# ASA.net
KiCad netlist of a schematic drawn in Altium Designer
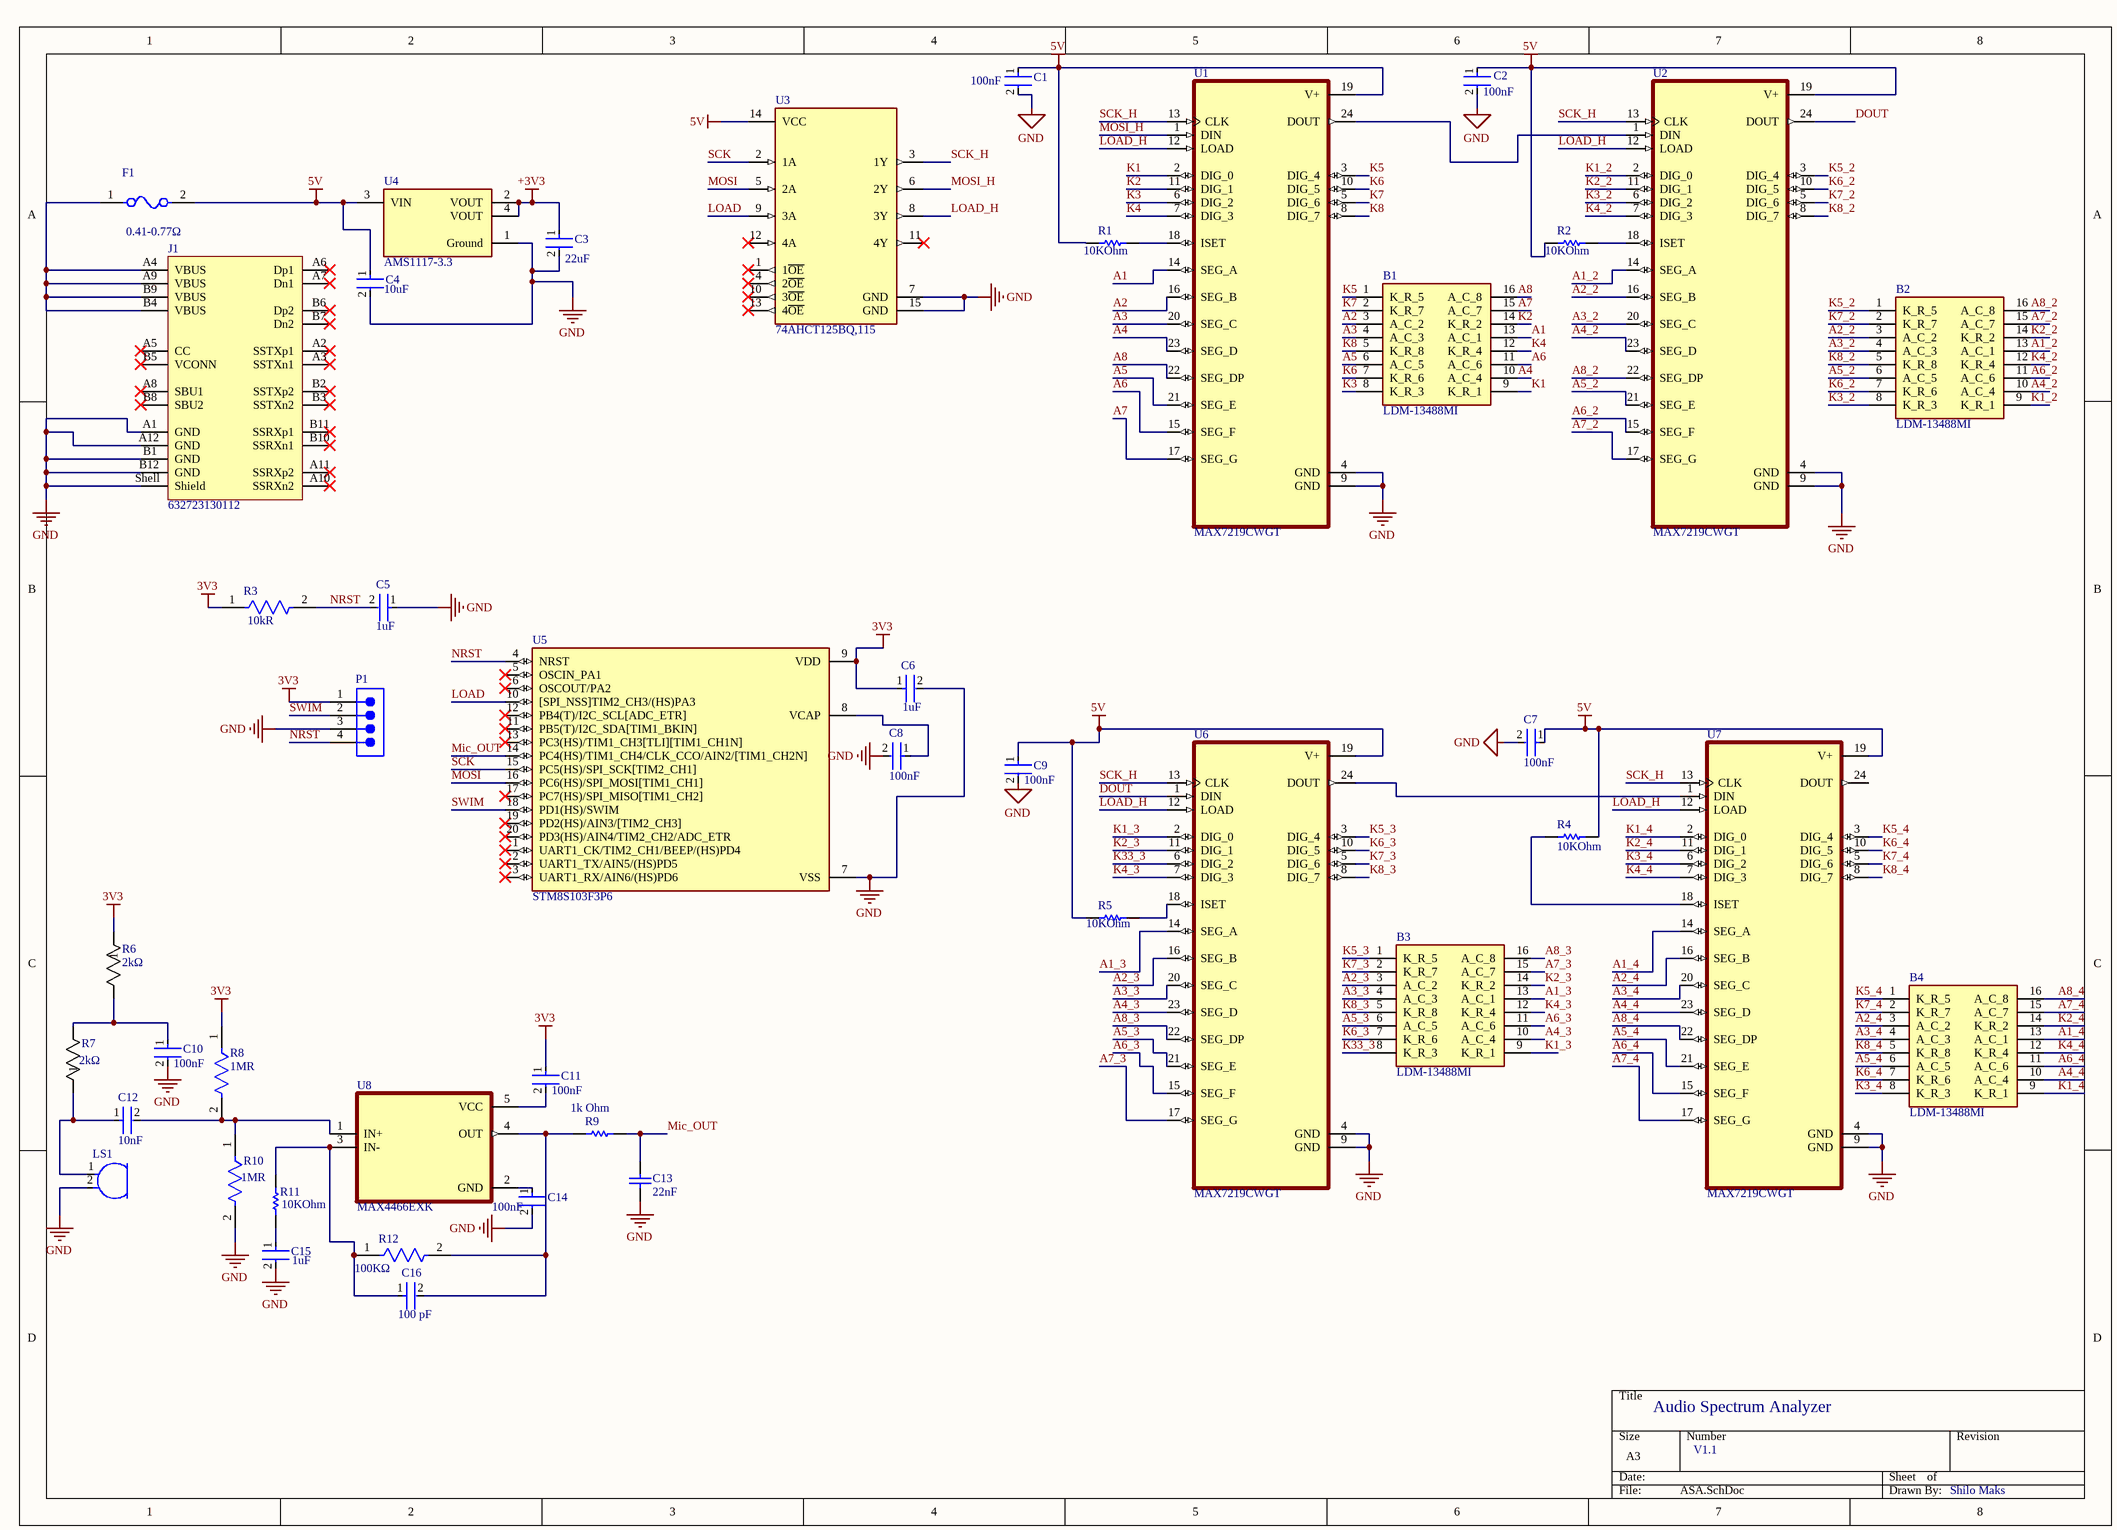
[diagram p0: ASA.SchDoc]

(export (version "E")
  (design (tool "Eeschema 10.0.6"))
  (components
    (comp (ref "B1")
      (value "LDM-13488MI")
      (footprint "LDM13488MI")
      (description "LED MATRIX 8X8 1.3\" 630NM RED CC")
      (fields (field (name "MOUSER PART NUMBER") "696-LDM-13488MI"))
      (libsource (lib "LDM-13488MI") (part "LDM-13488MI"))
    )
    (comp (ref "B2")
      (value "LDM-13488MI")
      (footprint "LDM13488MI")
      (description "LED MATRIX 8X8 1.3\" 630NM RED CC")
      (fields (field (name "MOUSER PART NUMBER") "696-LDM-13488MI"))
      (libsource (lib "LDM-13488MI") (part "LDM-13488MI"))
    )
    (comp (ref "B3")
      (value "LDM-13488MI")
      (footprint "LDM13488MI")
      (description "LED MATRIX 8X8 1.3\" 630NM RED CC")
      (fields (field (name "MOUSER PART NUMBER") "696-LDM-13488MI"))
      (libsource (lib "LDM-13488MI") (part "LDM-13488MI"))
    )
    (comp (ref "B4")
      (value "LDM-13488MI")
      (footprint "LDM13488MI")
      (description "LED MATRIX 8X8 1.3\" 630NM RED CC")
      (fields (field (name "MOUSER PART NUMBER") "696-LDM-13488MI"))
      (libsource (lib "LDM-13488MI") (part "LDM-13488MI"))
    )
    (comp (ref "C1")
      (value "HMK316B7104ML-T")
      (footprint "FP-1206-L_3_2_0_15-W_1_6-IPC_A")
      (description "None")
      (fields (field (name "CAPACITANCE") "100nF") (field (name "TOLERANCE") "20%"))
      (libsource (lib "Altium Content Vault") (part "02cd4be3c70576c341d710602a673aa"))
    )
    (comp (ref "C2")
      (value "HMK316B7104ML-T")
      (footprint "FP-1206-L_3_2_0_15-W_1_6-IPC_A")
      (description "None")
      (fields (field (name "CAPACITANCE") "100nF") (field (name "TOLERANCE") "20%"))
      (libsource (lib "Altium Content Vault") (part "02cd4be3c70576c341d710602a673aa"))
    )
    (comp (ref "C3")
      (value "CC0603MRX5R5BB226")
      (footprint "FP-CC0603-DC-MFG")
      (description "CAP CER 22UF 6.3V X5R 0603")
      (fields (field (name "TOLERANCE") "20%") (field (name "CAPACITANCE") "22uF"))
      (libsource (lib "Altium Content Vault") (part "b4654b650e69147ec39a6b967a45e02"))
    )
    (comp (ref "C4")
      (value "CL21A106MPFNNNF")
      (footprint "FP-CL21-IPC_C")
      (description "CL21 Series 0805 10uF 10V ±20% Tolerance X5R Multilayer Ceramic Chip Capacitor")
      (fields (field (name "TOLERANCE") "20%") (field (name "CAPACITANCE") "10uF"))
      (libsource (lib "Altium Content Vault") (part "b4654b650e69147ec39a6b967a45e02"))
    )
    (comp (ref "C5")
      (value "CL21F105ZAFNNNF")
      (footprint "FP-CL21-IPC_B")
      (description "CL21 Series 0805 1uF 25V -20/+80% Tolerance Y5V Multilayer Ceramic Chip Capacitor")
      (fields (field (name "CAPACITANCE") "1uF") (field (name "TOLERANCE") "80%"))
      (libsource (lib "Altium Content Vault") (part "b4654b650e69147ec39a6b967a45e02"))
    )
    (comp (ref "C6")
      (value "CL21F105ZAFNNNF")
      (footprint "FP-CL21-IPC_B")
      (description "CL21 Series 0805 1uF 25V -20/+80% Tolerance Y5V Multilayer Ceramic Chip Capacitor")
      (fields (field (name "CAPACITANCE") "1uF") (field (name "TOLERANCE") "80%"))
      (libsource (lib "Altium Content Vault") (part "b4654b650e69147ec39a6b967a45e02"))
    )
    (comp (ref "C7")
      (value "HMK316B7104ML-T")
      (footprint "FP-1206-L_3_2_0_15-W_1_6-IPC_A")
      (description "None")
      (fields (field (name "CAPACITANCE") "100nF") (field (name "TOLERANCE") "20%"))
      (libsource (lib "Altium Content Vault") (part "02cd4be3c70576c341d710602a673aa"))
    )
    (comp (ref "C8")
      (value "HMK316B7104ML-T")
      (footprint "FP-1206-L_3_2_0_15-W_1_6-IPC_A")
      (description "None")
      (fields (field (name "CAPACITANCE") "100nF") (field (name "TOLERANCE") "20%"))
      (libsource (lib "Altium Content Vault") (part "02cd4be3c70576c341d710602a673aa"))
    )
    (comp (ref "C9")
      (value "HMK316B7104ML-T")
      (footprint "FP-1206-L_3_2_0_15-W_1_6-IPC_A")
      (description "None")
      (fields (field (name "CAPACITANCE") "100nF") (field (name "TOLERANCE") "20%"))
      (libsource (lib "Altium Content Vault") (part "02cd4be3c70576c341d710602a673aa"))
    )
    (comp (ref "C10")
      (value "HMK316B7104ML-T")
      (footprint "FP-1206-L_3_2_0_15-W_1_6-IPC_A")
      (description "None")
      (fields (field (name "CAPACITANCE") "100nF") (field (name "TOLERANCE") "20%"))
      (libsource (lib "Altium Content Vault") (part "02cd4be3c70576c341d710602a673aa"))
    )
    (comp (ref "C11")
      (value "HMK316B7104ML-T")
      (footprint "FP-1206-L_3_2_0_15-W_1_6-IPC_A")
      (description "None")
      (fields (field (name "CAPACITANCE") "100nF") (field (name "TOLERANCE") "20%"))
      (libsource (lib "Altium Content Vault") (part "02cd4be3c70576c341d710602a673aa"))
    )
    (comp (ref "C12")
      (value "CGA3E2X8R2A103K080AD")
      (footprint "FP-CGA3E-0_3-0_1-IPC_A")
      (description "Cap Ceramic 10nF 100V X8R 10% Pad SMD 0603 +150°C Automotive T/R")
      (fields (field (name "CAPACITANCE") "10nF") (field (name "TOLERANCE") "10%"))
      (libsource (lib "Altium Content Vault") (part "b4654b650e69147ec39a6b967a45e02"))
    )
    (comp (ref "C13")
      (value "22nF")
      (footprint "CAPC1608X92X38NL15T08")
      (fields (field (name "MANUFACTURER") "Vitramon") (field (name "PART NUMBER") "VJ0603Y223KXAAC"))
      (libsource (lib "Altium Content Vault") (part "CAP"))
    )
    (comp (ref "C14")
      (value "HMK316B7104ML-T")
      (footprint "FP-1206-L_3_2_0_15-W_1_6-IPC_A")
      (description "None")
      (fields (field (name "CAPACITANCE") "100nF") (field (name "TOLERANCE") "20%"))
      (libsource (lib "Altium Content Vault") (part "02cd4be3c70576c341d710602a673aa"))
    )
    (comp (ref "C15")
      (value "CL21F105ZAFNNNF")
      (footprint "FP-CL21-IPC_B")
      (description "CL21 Series 0805 1uF 25V -20/+80% Tolerance Y5V Multilayer Ceramic Chip Capacitor")
      (fields (field (name "CAPACITANCE") "1uF") (field (name "TOLERANCE") "80%"))
      (libsource (lib "Altium Content Vault") (part "b4654b650e69147ec39a6b967a45e02"))
    )
    (comp (ref "C16")
      (value "C0402C101K5GACTU")
      (footprint "FP-C0402-BB-MFG")
      (description "CAP CER 100PF 50V 10% NP0 0402")
      (fields
        (field (name "TOLERANCE") "0.1")
        (field (name "CAPACITANCE") "100 pF")
        (field (name "MANUFACTURER") "Kemet")
      )
      (libsource (lib "Altium Content Vault") (part "b4654b650e69147ec39a6b967a45e02"))
    )
    (comp (ref "F1")
      (value "MF-R050")
      (footprint "FP-MF-R050-MFG")
      (description "PTC RESET FUSE 60V 500MA RADIAL")
      (fields
        (field (name "OCTOPART") "https://octopart.com/mf-r050-bourns-19418")
        (field (name "RESISTANCE") "0.41-0.77Ω")
        (field (name "MANUFACTURER") "Bourns")
      )
      (libsource (lib "Altium Content Vault") (part "5bcf9b9f640e542cf0359d10258e979"))
    )
    (comp (ref "J1")
      (value "632723130112")
      (footprint "632723130112")
      (description "WR-COM_USB 3.1_TYPE C_HORIZONTAL")
      (libsource (lib "Altium Content Vault") (part "USB 3.1_Type C_Receptacle_1 Port"))
    )
    (comp (ref "LS1")
      (value "POM-2738P-R")
      (footprint "FP-POM-2738P-R-MFG")
      (description "MIC COND ANALOG OMNI -38DB")
      (fields
        (field (name "MANUFACTURER") "PUI Audio, Inc.")
        (field (name "OCTOPART") "https://octopart.com/pom-2738p-r-pui+audio-19251807")
      )
      (libsource (lib "Altium Content Vault") (part "b2bcf75ddc372d3ce9fb98e3c3a2780"))
    )
    (comp (ref "P1")
      (value "61300411021")
      (footprint "61300411021")
      (libsource (lib "Altium Content Vault") (part "Header_Male_1R_04P"))
    )
    (comp (ref "R1")
      (value "10KOhm")
      (footprint "RESC1206(3216)_M")
      (description "10K 0.25W 5% 1206 (3216 Metric)  SMD")
      (fields (field (name "POWER") "0.25 W") (field (name "TOLERANCE") "5 %"))
      (libsource (lib "Altium Content Vault") (part "RES"))
    )
    (comp (ref "R2")
      (value "10KOhm")
      (footprint "RESC1206(3216)_M")
      (description "10K 0.25W 5% 1206 (3216 Metric)  SMD")
      (fields (field (name "POWER") "0.25 W") (field (name "TOLERANCE") "5 %"))
      (libsource (lib "Altium Content Vault") (part "RES"))
    )
    (comp (ref "R3")
      (value "CR2010-JW-103ELF")
      (footprint "FP-CR2010-IPC_C")
      (description "Thick Film Chip Resistors 2010 10kΩ 0.5W 5% 200ppm/°C")
      (fields (field (name "TOLERANCE") "5%") (field (name "RESISTANCE") "10kR"))
      (libsource (lib "Altium Content Vault") (part "1029c3af85768c4190bb7ad29bc67b5"))
    )
    (comp (ref "R4")
      (value "10KOhm")
      (footprint "RESC1206(3216)_M")
      (description "10K 0.25W 5% 1206 (3216 Metric)  SMD")
      (fields (field (name "POWER") "0.25 W") (field (name "TOLERANCE") "5 %"))
      (libsource (lib "Altium Content Vault") (part "RES"))
    )
    (comp (ref "R5")
      (value "10KOhm")
      (footprint "RESC1206(3216)_M")
      (description "10K 0.25W 5% 1206 (3216 Metric)  SMD")
      (fields (field (name "POWER") "0.25 W") (field (name "TOLERANCE") "5 %"))
      (libsource (lib "Altium Content Vault") (part "RES"))
    )
    (comp (ref "R6")
      (value "MCA12060D2001BP100")
      (footprint "MCA 1206_VIS")
      (fields (field (name "RESISTANCE") "2kΩ") (field (name "TOLERANCE") "0.1%"))
      (libsource (lib "Altium Content Vault") (part "MCA12060D2001BP100"))
    )
    (comp (ref "R7")
      (value "MCA12060D2001BP100")
      (footprint "MCA 1206_VIS")
      (fields (field (name "RESISTANCE") "2kΩ") (field (name "TOLERANCE") "0.1%"))
      (libsource (lib "Altium Content Vault") (part "MCA12060D2001BP100"))
    )
    (comp (ref "R8")
      (value "CRCW06031M00JNEAHP")
      (footprint "FP-CRCW0603-HPe3-IPC_A")
      (description "RES Thick Film, 1MΩ, 5%, 0.33W, 200ppm/°C, 0603")
      (fields (field (name "TOLERANCE") "5%") (field (name "RESISTANCE") "1MR"))
      (libsource (lib "Altium Content Vault") (part "1029c3af85768c4190bb7ad29bc67b5"))
    )
    (comp (ref "R9")
      (value "1k Ohm")
      (footprint "RESC2010(5025)_L")
      (description "1K 0.75W 5% 2010 (5025 Metric)  SMD")
      (fields (field (name "TOLERANCE") "5 %") (field (name "POWER") "0.75 W"))
      (libsource (lib "Altium Content Vault") (part "RES"))
    )
    (comp (ref "R10")
      (value "CRCW06031M00JNEAHP")
      (footprint "FP-CRCW0603-HPe3-IPC_A")
      (description "RES Thick Film, 1MΩ, 5%, 0.33W, 200ppm/°C, 0603")
      (fields (field (name "TOLERANCE") "5%") (field (name "RESISTANCE") "1MR"))
      (libsource (lib "Altium Content Vault") (part "1029c3af85768c4190bb7ad29bc67b5"))
    )
    (comp (ref "R11")
      (value "10KOhm")
      (footprint "RESC1206(3216)_M")
      (description "10K 0.25W 5% 1206 (3216 Metric)  SMD")
      (fields (field (name "POWER") "0.25 W") (field (name "TOLERANCE") "5 %"))
      (libsource (lib "Altium Content Vault") (part "RES"))
    )
    (comp (ref "R12")
      (value "RT1206DRE07100KL")
      (footprint "FP-RT1206-MFG")
      (description "RES SMD 100K OHM 0.5% 1/4W 1206")
      (fields
        (field (name "MANUFACTURER") "Yageo")
        (field (name "OCTOPART") "https://octopart.com/rt1206dre07100kl-yageo-1189867")
        (field (name "RESISTANCE") "100KΩ")
      )
      (libsource (lib "Altium Content Vault") (part "1029c3af85768c4190bb7ad29bc67b5"))
    )
    (comp (ref "U1")
      (value "MAX7219CWGT")
      (footprint "SOIC127P1032X265-24N")
      (description "IC DRVR 7 SEGMNT 8 DIGIT 24SOIC")
      (fields (field (name "MF") "Analog Devices") (field (name "MP") "MAX7219CWG+"))
      (libsource (lib "MAX7219CWGT") (part "MAX7219CWGT"))
    )
    (comp (ref "U2")
      (value "MAX7219CWGT")
      (footprint "SOIC127P1032X265-24N")
      (description "IC DRVR 7 SEGMNT 8 DIGIT 24SOIC")
      (fields (field (name "MF") "Analog Devices") (field (name "MP") "MAX7219CWG+"))
      (libsource (lib "MAX7219CWGT") (part "MAX7219CWGT"))
    )
    (comp (ref "U3")
      (value "74AHCT125BQ,115")
      (footprint "FP-SOT762-1-MFG")
      (description "IC BUFF NON-INVERT 5.5V 14DHVQFN")
      (libsource (lib "Altium Content Vault") (part "44bc387498ed07ffdea7b785a19f619"))
    )
    (comp (ref "U4")
      (value "AMS1117-3.3")
      (footprint "FP-AMS1117-IPC_C")
      (description "LDO Voltage Regulators 1A, 3.3V")
      (fields
        (field (name "OCTOPART") "https://octopart.com/ams1117-3.3-advanced+monolithic+systems-25899300")
        (field (name "MANUFACTURER") "Advanced Monolithic Systems")
      )
      (libsource (lib "Altium Content Vault") (part "8bdbb5f8e77002000e30dd2845d0354"))
    )
    (comp (ref "U5")
      (value "STM8S103F3P6")
      (footprint "SOP65P640X120-20N")
      (description "STM8 series Microcontroller IC 8-Bit 16MHz 8KB (8K x 8) FLASH 20-TSSOP")
      (fields (field (name "MF") "STMicroelectronics"))
      (libsource (lib "STM8S103F3P6") (part "STM8S103F3P6"))
    )
    (comp (ref "U6")
      (value "MAX7219CWGT")
      (footprint "SOIC127P1032X265-24N")
      (description "IC DRVR 7 SEGMNT 8 DIGIT 24SOIC")
      (fields (field (name "MF") "Analog Devices") (field (name "MP") "MAX7219CWG+"))
      (libsource (lib "MAX7219CWGT") (part "MAX7219CWGT"))
    )
    (comp (ref "U7")
      (value "MAX7219CWGT")
      (footprint "SOIC127P1032X265-24N")
      (description "IC DRVR 7 SEGMNT 8 DIGIT 24SOIC")
      (fields (field (name "MF") "Analog Devices") (field (name "MP") "MAX7219CWG+"))
      (libsource (lib "MAX7219CWGT") (part "MAX7219CWGT"))
    )
    (comp (ref "U8")
      (value "MAX4466EXK")
      (footprint "SOT65P210X110-5N")
      (description "Audio Amp Microphone 1-CH Mono Class-AB 5-Pin SC-70 T/R")
      (fields (field (name "MF") "Analog Devices") (field (name "MP") "MAX4466EXK+T"))
      (libsource (lib "MAX4466EXK") (part "MAX4466EXK"))
    )
  )
  (nets
    (net (code "1") (name "+3V3") (class "Default")
      (node (ref "C3") (pin "1") (pinfunction "1_1") (pintype "passive"))
      (node (ref "U4") (pin "2") (pinfunction "VOUT_2") (pintype "passive"))
      (node (ref "U4") (pin "4") (pinfunction "VOUT_4") (pintype "passive"))
    )
    (net (code "2") (name "/DOUT") (class "Default")
      (node (ref "U2") (pin "24") (pinfunction "DOUT_24") (pintype "output"))
      (node (ref "U6") (pin "1") (pinfunction "DIN_1") (pintype "input"))
    )
    (net (code "3") (name "/K1") (class "Default")
      (node (ref "B1") (pin "9") (pinfunction "K_R_1_9") (pintype "passive"))
      (node (ref "U1") (pin "2") (pinfunction "DIG_0_2") (pintype "bidirectional"))
    )
    (net (code "4") (name "/K1_2") (class "Default")
      (node (ref "B2") (pin "9") (pinfunction "K_R_1_9") (pintype "passive"))
      (node (ref "U2") (pin "2") (pinfunction "DIG_0_2") (pintype "bidirectional"))
    )
    (net (code "5") (name "/K1_3") (class "Default")
      (node (ref "B3") (pin "9") (pinfunction "K_R_1_9") (pintype "passive"))
      (node (ref "U6") (pin "2") (pinfunction "DIG_0_2") (pintype "bidirectional"))
    )
    (net (code "6") (name "/K1_4") (class "Default")
      (node (ref "B4") (pin "9") (pinfunction "K_R_1_9") (pintype "passive"))
      (node (ref "U7") (pin "2") (pinfunction "DIG_0_2") (pintype "bidirectional"))
    )
    (net (code "7") (name "/K2") (class "Default")
      (node (ref "B1") (pin "14") (pinfunction "K_R_2_14") (pintype "passive"))
      (node (ref "U1") (pin "11") (pinfunction "DIG_1_11") (pintype "bidirectional"))
    )
    (net (code "8") (name "/K2_2") (class "Default")
      (node (ref "B2") (pin "14") (pinfunction "K_R_2_14") (pintype "passive"))
      (node (ref "U2") (pin "11") (pinfunction "DIG_1_11") (pintype "bidirectional"))
    )
    (net (code "9") (name "/K2_3") (class "Default")
      (node (ref "B3") (pin "14") (pinfunction "K_R_2_14") (pintype "passive"))
      (node (ref "U6") (pin "11") (pinfunction "DIG_1_11") (pintype "bidirectional"))
    )
    (net (code "10") (name "/K2_4") (class "Default")
      (node (ref "B4") (pin "14") (pinfunction "K_R_2_14") (pintype "passive"))
      (node (ref "U7") (pin "11") (pinfunction "DIG_1_11") (pintype "bidirectional"))
    )
    (net (code "11") (name "/K3") (class "Default")
      (node (ref "B1") (pin "8") (pinfunction "K_R_3_8") (pintype "passive"))
      (node (ref "U1") (pin "6") (pinfunction "DIG_2_6") (pintype "bidirectional"))
    )
    (net (code "12") (name "/K3_2") (class "Default")
      (node (ref "B2") (pin "8") (pinfunction "K_R_3_8") (pintype "passive"))
      (node (ref "U2") (pin "6") (pinfunction "DIG_2_6") (pintype "bidirectional"))
    )
    (net (code "13") (name "/K3_4") (class "Default")
      (node (ref "B4") (pin "8") (pinfunction "K_R_3_8") (pintype "passive"))
      (node (ref "U7") (pin "6") (pinfunction "DIG_2_6") (pintype "bidirectional"))
    )
    (net (code "14") (name "/K4") (class "Default")
      (node (ref "B1") (pin "12") (pinfunction "K_R_4_12") (pintype "passive"))
      (node (ref "U1") (pin "7") (pinfunction "DIG_3_7") (pintype "bidirectional"))
    )
    (net (code "15") (name "/K4_2") (class "Default")
      (node (ref "B2") (pin "12") (pinfunction "K_R_4_12") (pintype "passive"))
      (node (ref "U2") (pin "7") (pinfunction "DIG_3_7") (pintype "bidirectional"))
    )
    (net (code "16") (name "/K4_3") (class "Default")
      (node (ref "B3") (pin "12") (pinfunction "K_R_4_12") (pintype "passive"))
      (node (ref "U6") (pin "7") (pinfunction "DIG_3_7") (pintype "bidirectional"))
    )
    (net (code "17") (name "/K4_4") (class "Default")
      (node (ref "B4") (pin "12") (pinfunction "K_R_4_12") (pintype "passive"))
      (node (ref "U7") (pin "7") (pinfunction "DIG_3_7") (pintype "bidirectional"))
    )
    (net (code "18") (name "/K5") (class "Default")
      (node (ref "B1") (pin "1") (pinfunction "K_R_5_1") (pintype "passive"))
      (node (ref "U1") (pin "3") (pinfunction "DIG_4_3") (pintype "bidirectional"))
    )
    (net (code "19") (name "/K5_2") (class "Default")
      (node (ref "B2") (pin "1") (pinfunction "K_R_5_1") (pintype "passive"))
      (node (ref "U2") (pin "3") (pinfunction "DIG_4_3") (pintype "bidirectional"))
    )
    (net (code "20") (name "/K5_3") (class "Default")
      (node (ref "B3") (pin "1") (pinfunction "K_R_5_1") (pintype "passive"))
      (node (ref "U6") (pin "3") (pinfunction "DIG_4_3") (pintype "bidirectional"))
    )
    (net (code "21") (name "/K5_4") (class "Default")
      (node (ref "B4") (pin "1") (pinfunction "K_R_5_1") (pintype "passive"))
      (node (ref "U7") (pin "3") (pinfunction "DIG_4_3") (pintype "bidirectional"))
    )
    (net (code "22") (name "/K6") (class "Default")
      (node (ref "B1") (pin "7") (pinfunction "K_R_6_7") (pintype "passive"))
      (node (ref "U1") (pin "10") (pinfunction "DIG_5_10") (pintype "bidirectional"))
    )
    (net (code "23") (name "/K6_2") (class "Default")
      (node (ref "B2") (pin "7") (pinfunction "K_R_6_7") (pintype "passive"))
      (node (ref "U2") (pin "10") (pinfunction "DIG_5_10") (pintype "bidirectional"))
    )
    (net (code "24") (name "/K6_3") (class "Default")
      (node (ref "B3") (pin "7") (pinfunction "K_R_6_7") (pintype "passive"))
      (node (ref "U6") (pin "10") (pinfunction "DIG_5_10") (pintype "bidirectional"))
    )
    (net (code "25") (name "/K6_4") (class "Default")
      (node (ref "B4") (pin "7") (pinfunction "K_R_6_7") (pintype "passive"))
      (node (ref "U7") (pin "10") (pinfunction "DIG_5_10") (pintype "bidirectional"))
    )
    (net (code "26") (name "/K7") (class "Default")
      (node (ref "B1") (pin "2") (pinfunction "K_R_7_2") (pintype "passive"))
      (node (ref "U1") (pin "5") (pinfunction "DIG_6_5") (pintype "bidirectional"))
    )
    (net (code "27") (name "/K7_2") (class "Default")
      (node (ref "B2") (pin "2") (pinfunction "K_R_7_2") (pintype "passive"))
      (node (ref "U2") (pin "5") (pinfunction "DIG_6_5") (pintype "bidirectional"))
    )
    (net (code "28") (name "/K7_3") (class "Default")
      (node (ref "B3") (pin "2") (pinfunction "K_R_7_2") (pintype "passive"))
      (node (ref "U6") (pin "5") (pinfunction "DIG_6_5") (pintype "bidirectional"))
    )
    (net (code "29") (name "/K7_4") (class "Default")
      (node (ref "B4") (pin "2") (pinfunction "K_R_7_2") (pintype "passive"))
      (node (ref "U7") (pin "5") (pinfunction "DIG_6_5") (pintype "bidirectional"))
    )
    (net (code "30") (name "/K8") (class "Default")
      (node (ref "B1") (pin "5") (pinfunction "K_R_8_5") (pintype "passive"))
      (node (ref "U1") (pin "8") (pinfunction "DIG_7_8") (pintype "bidirectional"))
    )
    (net (code "31") (name "/K8_2") (class "Default")
      (node (ref "B2") (pin "5") (pinfunction "K_R_8_5") (pintype "passive"))
      (node (ref "U2") (pin "8") (pinfunction "DIG_7_8") (pintype "bidirectional"))
    )
    (net (code "32") (name "/K8_3") (class "Default")
      (node (ref "B3") (pin "5") (pinfunction "K_R_8_5") (pintype "passive"))
      (node (ref "U6") (pin "8") (pinfunction "DIG_7_8") (pintype "bidirectional"))
    )
    (net (code "33") (name "/K8_4") (class "Default")
      (node (ref "B4") (pin "5") (pinfunction "K_R_8_5") (pintype "passive"))
      (node (ref "U7") (pin "8") (pinfunction "DIG_7_8") (pintype "bidirectional"))
    )
    (net (code "34") (name "/K33_3") (class "Default")
      (node (ref "B3") (pin "8") (pinfunction "K_R_3_8") (pintype "passive"))
      (node (ref "U6") (pin "6") (pinfunction "DIG_2_6") (pintype "bidirectional"))
    )
    (net (code "35") (name "/LOAD") (class "Default")
      (node (ref "U3") (pin "9") (pinfunction "3A_9") (pintype "input"))
      (node (ref "U5") (pin "10") (pinfunction "[SPI_NSS]TIM2_CH3/(HS)PA3_10") (pintype "bidirectional"))
    )
    (net (code "36") (name "/LOAD_H") (class "Default")
      (node (ref "U1") (pin "12") (pinfunction "LOAD_12") (pintype "input"))
      (node (ref "U2") (pin "12") (pinfunction "LOAD_12") (pintype "input"))
      (node (ref "U3") (pin "8") (pinfunction "3Y_8") (pintype "output"))
      (node (ref "U6") (pin "12") (pinfunction "LOAD_12") (pintype "input"))
      (node (ref "U7") (pin "12") (pinfunction "LOAD_12") (pintype "input"))
    )
    (net (code "37") (name "/MOSI") (class "Default")
      (node (ref "U3") (pin "5") (pinfunction "2A_5") (pintype "input"))
      (node (ref "U5") (pin "16") (pinfunction "PC6(HS)/SPI_MOSI[TIM1_CH1]_16") (pintype "bidirectional"))
    )
    (net (code "38") (name "/MOSI_H") (class "Default")
      (node (ref "U1") (pin "1") (pinfunction "DIN_1") (pintype "input"))
      (node (ref "U3") (pin "6") (pinfunction "2Y_6") (pintype "output"))
    )
    (net (code "39") (name "/Mic_OUT") (class "Default")
      (node (ref "C13") (pin "2") (pinfunction "2_2") (pintype "passive"))
      (node (ref "R9") (pin "2") (pinfunction "2_2") (pintype "passive"))
      (node (ref "U5") (pin "14") (pinfunction "PC4(HS)/TIM1_CH4/CLK_CCO/AIN2/[TIM1_CH2N]_14") (pintype "bidirectional"))
    )
    (net (code "40") (name "/NRST") (class "Default")
      (node (ref "C5") (pin "2") (pinfunction "2_2") (pintype "passive"))
      (node (ref "P1") (pin "4") (pinfunction "4_4") (pintype "passive"))
      (node (ref "R3") (pin "2") (pinfunction "2_2") (pintype "passive"))
      (node (ref "U5") (pin "4") (pinfunction "NRST_4") (pintype "bidirectional"))
    )
    (net (code "41") (name "/SCK") (class "Default")
      (node (ref "U3") (pin "2") (pinfunction "1A_2") (pintype "input"))
      (node (ref "U5") (pin "15") (pinfunction "PC5(HS)/SPI_SCK[TIM2_CH1]_15") (pintype "bidirectional"))
    )
    (net (code "42") (name "/SCK_H") (class "Default")
      (node (ref "U1") (pin "13") (pinfunction "CLK_13") (pintype "input"))
      (node (ref "U2") (pin "13") (pinfunction "CLK_13") (pintype "input"))
      (node (ref "U3") (pin "3") (pinfunction "1Y_3") (pintype "output"))
      (node (ref "U6") (pin "13") (pinfunction "CLK_13") (pintype "input"))
      (node (ref "U7") (pin "13") (pinfunction "CLK_13") (pintype "input"))
    )
    (net (code "43") (name "/SWIM") (class "Default")
      (node (ref "P1") (pin "2") (pinfunction "2_2") (pintype "passive"))
      (node (ref "U5") (pin "18") (pinfunction "PD1(HS)/SWIM_18") (pintype "bidirectional"))
    )
    (net (code "44") (name "/А1") (class "Default")
      (node (ref "B1") (pin "13") (pinfunction "A_C_1_13") (pintype "passive"))
      (node (ref "U1") (pin "14") (pinfunction "SEG_A_14") (pintype "bidirectional"))
    )
    (net (code "45") (name "/А1_2") (class "Default")
      (node (ref "B2") (pin "13") (pinfunction "A_C_1_13") (pintype "passive"))
      (node (ref "U2") (pin "14") (pinfunction "SEG_A_14") (pintype "bidirectional"))
    )
    (net (code "46") (name "/А1_3") (class "Default")
      (node (ref "B3") (pin "13") (pinfunction "A_C_1_13") (pintype "passive"))
      (node (ref "U6") (pin "14") (pinfunction "SEG_A_14") (pintype "bidirectional"))
    )
    (net (code "47") (name "/А1_4") (class "Default")
      (node (ref "B4") (pin "13") (pinfunction "A_C_1_13") (pintype "passive"))
      (node (ref "U7") (pin "14") (pinfunction "SEG_A_14") (pintype "bidirectional"))
    )
    (net (code "48") (name "/А2") (class "Default")
      (node (ref "B1") (pin "3") (pinfunction "A_C_2_3") (pintype "passive"))
      (node (ref "U1") (pin "16") (pinfunction "SEG_B_16") (pintype "bidirectional"))
    )
    (net (code "49") (name "/А2_2") (class "Default")
      (node (ref "B2") (pin "3") (pinfunction "A_C_2_3") (pintype "passive"))
      (node (ref "U2") (pin "16") (pinfunction "SEG_B_16") (pintype "bidirectional"))
    )
    (net (code "50") (name "/А2_3") (class "Default")
      (node (ref "B3") (pin "3") (pinfunction "A_C_2_3") (pintype "passive"))
      (node (ref "U6") (pin "16") (pinfunction "SEG_B_16") (pintype "bidirectional"))
    )
    (net (code "51") (name "/А2_4") (class "Default")
      (node (ref "B4") (pin "3") (pinfunction "A_C_2_3") (pintype "passive"))
      (node (ref "U7") (pin "16") (pinfunction "SEG_B_16") (pintype "bidirectional"))
    )
    (net (code "52") (name "/А3") (class "Default")
      (node (ref "B1") (pin "4") (pinfunction "A_C_3_4") (pintype "passive"))
      (node (ref "U1") (pin "20") (pinfunction "SEG_C_20") (pintype "bidirectional"))
    )
    (net (code "53") (name "/А3_2") (class "Default")
      (node (ref "B2") (pin "4") (pinfunction "A_C_3_4") (pintype "passive"))
      (node (ref "U2") (pin "20") (pinfunction "SEG_C_20") (pintype "bidirectional"))
    )
    (net (code "54") (name "/А3_3") (class "Default")
      (node (ref "B3") (pin "4") (pinfunction "A_C_3_4") (pintype "passive"))
      (node (ref "U6") (pin "20") (pinfunction "SEG_C_20") (pintype "bidirectional"))
    )
    (net (code "55") (name "/А3_4") (class "Default")
      (node (ref "B4") (pin "4") (pinfunction "A_C_3_4") (pintype "passive"))
      (node (ref "U7") (pin "20") (pinfunction "SEG_C_20") (pintype "bidirectional"))
    )
    (net (code "56") (name "/А4") (class "Default")
      (node (ref "B1") (pin "10") (pinfunction "A_C_4_10") (pintype "passive"))
      (node (ref "U1") (pin "23") (pinfunction "SEG_D_23") (pintype "bidirectional"))
    )
    (net (code "57") (name "/А4_2") (class "Default")
      (node (ref "B2") (pin "10") (pinfunction "A_C_4_10") (pintype "passive"))
      (node (ref "U2") (pin "23") (pinfunction "SEG_D_23") (pintype "bidirectional"))
    )
    (net (code "58") (name "/А4_3") (class "Default")
      (node (ref "B3") (pin "10") (pinfunction "A_C_4_10") (pintype "passive"))
      (node (ref "U6") (pin "23") (pinfunction "SEG_D_23") (pintype "bidirectional"))
    )
    (net (code "59") (name "/А4_4") (class "Default")
      (node (ref "B4") (pin "10") (pinfunction "A_C_4_10") (pintype "passive"))
      (node (ref "U7") (pin "23") (pinfunction "SEG_D_23") (pintype "bidirectional"))
    )
    (net (code "60") (name "/А5") (class "Default")
      (node (ref "B1") (pin "6") (pinfunction "A_C_5_6") (pintype "passive"))
      (node (ref "U1") (pin "21") (pinfunction "SEG_E_21") (pintype "bidirectional"))
    )
    (net (code "61") (name "/А5_2") (class "Default")
      (node (ref "B2") (pin "6") (pinfunction "A_C_5_6") (pintype "passive"))
      (node (ref "U2") (pin "21") (pinfunction "SEG_E_21") (pintype "bidirectional"))
    )
    (net (code "62") (name "/А5_3") (class "Default")
      (node (ref "B3") (pin "6") (pinfunction "A_C_5_6") (pintype "passive"))
      (node (ref "U6") (pin "21") (pinfunction "SEG_E_21") (pintype "bidirectional"))
    )
    (net (code "63") (name "/А5_4") (class "Default")
      (node (ref "B4") (pin "6") (pinfunction "A_C_5_6") (pintype "passive"))
      (node (ref "U7") (pin "21") (pinfunction "SEG_E_21") (pintype "bidirectional"))
    )
    (net (code "64") (name "/А6") (class "Default")
      (node (ref "B1") (pin "11") (pinfunction "A_C_6_11") (pintype "passive"))
      (node (ref "U1") (pin "15") (pinfunction "SEG_F_15") (pintype "bidirectional"))
    )
    (net (code "65") (name "/А6_2") (class "Default")
      (node (ref "B2") (pin "11") (pinfunction "A_C_6_11") (pintype "passive"))
      (node (ref "U2") (pin "15") (pinfunction "SEG_F_15") (pintype "bidirectional"))
    )
    (net (code "66") (name "/А6_3") (class "Default")
      (node (ref "B3") (pin "11") (pinfunction "A_C_6_11") (pintype "passive"))
      (node (ref "U6") (pin "15") (pinfunction "SEG_F_15") (pintype "bidirectional"))
    )
    (net (code "67") (name "/А6_4") (class "Default")
      (node (ref "B4") (pin "11") (pinfunction "A_C_6_11") (pintype "passive"))
      (node (ref "U7") (pin "15") (pinfunction "SEG_F_15") (pintype "bidirectional"))
    )
    (net (code "68") (name "/А7") (class "Default")
      (node (ref "B1") (pin "15") (pinfunction "A_C_7_15") (pintype "passive"))
      (node (ref "U1") (pin "17") (pinfunction "SEG_G_17") (pintype "bidirectional"))
    )
    (net (code "69") (name "/А7_2") (class "Default")
      (node (ref "B2") (pin "15") (pinfunction "A_C_7_15") (pintype "passive"))
      (node (ref "U2") (pin "17") (pinfunction "SEG_G_17") (pintype "bidirectional"))
    )
    (net (code "70") (name "/А7_3") (class "Default")
      (node (ref "B3") (pin "15") (pinfunction "A_C_7_15") (pintype "passive"))
      (node (ref "U6") (pin "17") (pinfunction "SEG_G_17") (pintype "bidirectional"))
    )
    (net (code "71") (name "/А7_4") (class "Default")
      (node (ref "B4") (pin "15") (pinfunction "A_C_7_15") (pintype "passive"))
      (node (ref "U7") (pin "17") (pinfunction "SEG_G_17") (pintype "bidirectional"))
    )
    (net (code "72") (name "/А8") (class "Default")
      (node (ref "B1") (pin "16") (pinfunction "A_C_8_16") (pintype "passive"))
      (node (ref "U1") (pin "22") (pinfunction "SEG_DP_22") (pintype "bidirectional"))
    )
    (net (code "73") (name "/А8_2") (class "Default")
      (node (ref "B2") (pin "16") (pinfunction "A_C_8_16") (pintype "passive"))
      (node (ref "U2") (pin "22") (pinfunction "SEG_DP_22") (pintype "bidirectional"))
    )
    (net (code "74") (name "/А8_3") (class "Default")
      (node (ref "B3") (pin "16") (pinfunction "A_C_8_16") (pintype "passive"))
      (node (ref "U6") (pin "22") (pinfunction "SEG_DP_22") (pintype "bidirectional"))
    )
    (net (code "75") (name "/А8_4") (class "Default")
      (node (ref "B4") (pin "16") (pinfunction "A_C_8_16") (pintype "passive"))
      (node (ref "U7") (pin "22") (pinfunction "SEG_DP_22") (pintype "bidirectional"))
    )
    (net (code "76") (name "3V3") (class "Default")
      (node (ref "C11") (pin "1") (pinfunction "1_1") (pintype "passive"))
      (node (ref "C6") (pin "1") (pinfunction "1_1") (pintype "passive"))
      (node (ref "P1") (pin "1") (pinfunction "1_1") (pintype "passive"))
      (node (ref "R3") (pin "1") (pinfunction "1_1") (pintype "passive"))
      (node (ref "R6") (pin "1") (pinfunction "1_1") (pintype "passive"))
      (node (ref "R8") (pin "1") (pinfunction "1_1") (pintype "passive"))
      (node (ref "U5") (pin "9") (pinfunction "VDD_9") (pintype "power_in"))
    )
    (net (code "77") (name "5V") (class "Default")
      (node (ref "C1") (pin "1") (pinfunction "1_1") (pintype "passive"))
      (node (ref "C2") (pin "1") (pinfunction "1_1") (pintype "passive"))
      (node (ref "C4") (pin "1") (pinfunction "1_1") (pintype "passive"))
      (node (ref "C7") (pin "1") (pinfunction "1_1") (pintype "passive"))
      (node (ref "C9") (pin "1") (pinfunction "1_1") (pintype "passive"))
      (node (ref "F1") (pin "2") (pinfunction "2_2") (pintype "passive"))
      (node (ref "R1") (pin "2") (pinfunction "2_2") (pintype "passive"))
      (node (ref "R2") (pin "2") (pinfunction "2_2") (pintype "passive"))
      (node (ref "R4") (pin "1") (pinfunction "1_1") (pintype "passive"))
      (node (ref "R5") (pin "2") (pinfunction "2_2") (pintype "passive"))
      (node (ref "U1") (pin "19") (pinfunction "V+_19") (pintype "power_in"))
      (node (ref "U2") (pin "19") (pinfunction "V+_19") (pintype "power_in"))
      (node (ref "U3") (pin "14") (pinfunction "VCC_14") (pintype "power_in"))
      (node (ref "U4") (pin "3") (pinfunction "VIN_3") (pintype "power_in"))
      (node (ref "U6") (pin "19") (pinfunction "V+_19") (pintype "power_in"))
      (node (ref "U7") (pin "19") (pinfunction "V+_19") (pintype "power_in"))
    )
    (net (code "78") (name "GND") (class "Default")
      (node (ref "C1") (pin "2") (pinfunction "2_2") (pintype "passive"))
      (node (ref "C10") (pin "2") (pinfunction "2_2") (pintype "passive"))
      (node (ref "C13") (pin "1") (pinfunction "1_1") (pintype "passive"))
      (node (ref "C14") (pin "2") (pinfunction "2_2") (pintype "passive"))
      (node (ref "C15") (pin "2") (pinfunction "2_2") (pintype "passive"))
      (node (ref "C2") (pin "2") (pinfunction "2_2") (pintype "passive"))
      (node (ref "C3") (pin "2") (pinfunction "2_2") (pintype "passive"))
      (node (ref "C4") (pin "2") (pinfunction "2_2") (pintype "passive"))
      (node (ref "C5") (pin "1") (pinfunction "1_1") (pintype "passive"))
      (node (ref "C6") (pin "2") (pinfunction "2_2") (pintype "passive"))
      (node (ref "C7") (pin "2") (pinfunction "2_2") (pintype "passive"))
      (node (ref "C8") (pin "2") (pinfunction "2_2") (pintype "passive"))
      (node (ref "C9") (pin "2") (pinfunction "2_2") (pintype "passive"))
      (node (ref "J1") (pin "A1") (pinfunction "GND_A1") (pintype "passive"))
      (node (ref "J1") (pin "A12") (pinfunction "GND_A12") (pintype "passive"))
      (node (ref "J1") (pin "B1") (pinfunction "GND_B1") (pintype "passive"))
      (node (ref "J1") (pin "B12") (pinfunction "GND_B12") (pintype "passive"))
      (node (ref "J1") (pin "Shell") (pinfunction "Shield_Shell") (pintype "passive"))
      (node (ref "LS1") (pin "2") (pinfunction "C_2") (pintype "passive"))
      (node (ref "P1") (pin "3") (pinfunction "3_3") (pintype "passive"))
      (node (ref "R10") (pin "2") (pinfunction "2_2") (pintype "passive"))
      (node (ref "U1") (pin "4") (pinfunction "GND_4") (pintype "power_in"))
      (node (ref "U1") (pin "9") (pinfunction "GND_9") (pintype "power_in"))
      (node (ref "U2") (pin "4") (pinfunction "GND_4") (pintype "power_in"))
      (node (ref "U2") (pin "9") (pinfunction "GND_9") (pintype "power_in"))
      (node (ref "U3") (pin "15") (pinfunction "GND_15") (pintype "power_in"))
      (node (ref "U3") (pin "7") (pinfunction "GND_7") (pintype "power_in"))
      (node (ref "U4") (pin "1") (pinfunction "Ground_1") (pintype "power_in"))
      (node (ref "U5") (pin "7") (pinfunction "VSS_7") (pintype "power_in"))
      (node (ref "U6") (pin "4") (pinfunction "GND_4") (pintype "power_in"))
      (node (ref "U6") (pin "9") (pinfunction "GND_9") (pintype "power_in"))
      (node (ref "U7") (pin "4") (pinfunction "GND_4") (pintype "power_in"))
      (node (ref "U7") (pin "9") (pinfunction "GND_9") (pintype "power_in"))
    )
    (net (code "79") (name "Net-(C10-Pad1)") (class "Default")
      (node (ref "C10") (pin "1") (pinfunction "1_1") (pintype "passive"))
      (node (ref "R6") (pin "2") (pinfunction "2_2") (pintype "passive"))
      (node (ref "R7") (pin "2") (pinfunction "2_2") (pintype "passive"))
    )
    (net (code "80") (name "Net-(C15-Pad1)") (class "Default")
      (node (ref "C15") (pin "1") (pinfunction "1_1") (pintype "passive"))
      (node (ref "R11") (pin "1") (pinfunction "1_1") (pintype "passive"))
    )
    (net (code "81") (name "Net-(F1-Pad1)") (class "Default")
      (node (ref "F1") (pin "1") (pinfunction "1_1") (pintype "passive"))
      (node (ref "J1") (pin "A4") (pinfunction "VBUS_A4") (pintype "passive"))
      (node (ref "J1") (pin "A9") (pinfunction "VBUS_A9") (pintype "passive"))
      (node (ref "J1") (pin "B4") (pinfunction "VBUS_B4") (pintype "passive"))
      (node (ref "J1") (pin "B9") (pinfunction "VBUS_B9") (pintype "passive"))
    )
    (net (code "82") (name "Net-(LS1-A)") (class "Default")
      (node (ref "C12") (pin "1") (pinfunction "1_1") (pintype "passive"))
      (node (ref "LS1") (pin "1") (pinfunction "A_1") (pintype "passive"))
      (node (ref "R7") (pin "1") (pinfunction "1_1") (pintype "passive"))
    )
    (net (code "83") (name "Net-(U1-DOUT)") (class "Default")
      (node (ref "U1") (pin "24") (pinfunction "DOUT_24") (pintype "output"))
      (node (ref "U2") (pin "1") (pinfunction "DIN_1") (pintype "input"))
    )
    (net (code "84") (name "Net-(U1-ISET)") (class "Default")
      (node (ref "R1") (pin "1") (pinfunction "1_1") (pintype "passive"))
      (node (ref "U1") (pin "18") (pinfunction "ISET_18") (pintype "bidirectional"))
    )
    (net (code "85") (name "Net-(U2-ISET)") (class "Default")
      (node (ref "R2") (pin "1") (pinfunction "1_1") (pintype "passive"))
      (node (ref "U2") (pin "18") (pinfunction "ISET_18") (pintype "bidirectional"))
    )
    (net (code "86") (name "Net-(U5-VCAP)") (class "Default")
      (node (ref "C8") (pin "1") (pinfunction "1_1") (pintype "passive"))
      (node (ref "U5") (pin "8") (pinfunction "VCAP_8") (pintype "passive"))
    )
    (net (code "87") (name "Net-(U6-DOUT)") (class "Default")
      (node (ref "U6") (pin "24") (pinfunction "DOUT_24") (pintype "output"))
      (node (ref "U7") (pin "1") (pinfunction "DIN_1") (pintype "input"))
    )
    (net (code "88") (name "Net-(U6-ISET)") (class "Default")
      (node (ref "R5") (pin "1") (pinfunction "1_1") (pintype "passive"))
      (node (ref "U6") (pin "18") (pinfunction "ISET_18") (pintype "bidirectional"))
    )
    (net (code "89") (name "Net-(U7-ISET)") (class "Default")
      (node (ref "R4") (pin "2") (pinfunction "2_2") (pintype "passive"))
      (node (ref "U7") (pin "18") (pinfunction "ISET_18") (pintype "bidirectional"))
    )
    (net (code "90") (name "Net-(U8-GND)") (class "Default")
      (node (ref "C14") (pin "1") (pinfunction "1_1") (pintype "passive"))
      (node (ref "U8") (pin "2") (pinfunction "GND_2") (pintype "power_in"))
    )
    (net (code "91") (name "Net-(U8-IN+)") (class "Default")
      (node (ref "C12") (pin "2") (pinfunction "2_2") (pintype "passive"))
      (node (ref "R10") (pin "1") (pinfunction "1_1") (pintype "passive"))
      (node (ref "R8") (pin "2") (pinfunction "2_2") (pintype "passive"))
      (node (ref "U8") (pin "1") (pinfunction "IN+_1") (pintype "passive"))
    )
    (net (code "92") (name "Net-(U8-IN-)") (class "Default")
      (node (ref "C16") (pin "1") (pinfunction "1_1") (pintype "passive"))
      (node (ref "R11") (pin "2") (pinfunction "2_2") (pintype "passive"))
      (node (ref "R12") (pin "1") (pinfunction "1_1") (pintype "passive"))
      (node (ref "U8") (pin "3") (pinfunction "IN-_3") (pintype "passive"))
    )
    (net (code "93") (name "Net-(U8-OUT)") (class "Default")
      (node (ref "C16") (pin "2") (pinfunction "2_2") (pintype "passive"))
      (node (ref "R12") (pin "2") (pinfunction "2_2") (pintype "passive"))
      (node (ref "R9") (pin "1") (pinfunction "1_1") (pintype "passive"))
      (node (ref "U8") (pin "4") (pinfunction "OUT_4") (pintype "output"))
    )
    (net (code "94") (name "Net-(U8-VCC)") (class "Default")
      (node (ref "C11") (pin "2") (pinfunction "2_2") (pintype "passive"))
      (node (ref "U8") (pin "5") (pinfunction "VCC_5") (pintype "power_in"))
    )
    (net (code "95") (name "unconnected-(J1-CC-PadA5)") (class "Default")
      (node (ref "J1") (pin "A5") (pinfunction "CC_A5") (pintype "passive+no_connect"))
    )
    (net (code "96") (name "unconnected-(J1-Dn1-PadA7)") (class "Default")
      (node (ref "J1") (pin "A7") (pinfunction "Dn1_A7") (pintype "passive+no_connect"))
    )
    (net (code "97") (name "unconnected-(J1-Dn2-PadB7)") (class "Default")
      (node (ref "J1") (pin "B7") (pinfunction "Dn2_B7") (pintype "passive+no_connect"))
    )
    (net (code "98") (name "unconnected-(J1-Dp1-PadA6)") (class "Default")
      (node (ref "J1") (pin "A6") (pinfunction "Dp1_A6") (pintype "passive+no_connect"))
    )
    (net (code "99") (name "unconnected-(J1-Dp2-PadB6)") (class "Default")
      (node (ref "J1") (pin "B6") (pinfunction "Dp2_B6") (pintype "passive+no_connect"))
    )
    (net (code "100") (name "unconnected-(J1-SBU1-PadA8)") (class "Default")
      (node (ref "J1") (pin "A8") (pinfunction "SBU1_A8") (pintype "passive+no_connect"))
    )
    (net (code "101") (name "unconnected-(J1-SBU2-PadB8)") (class "Default")
      (node (ref "J1") (pin "B8") (pinfunction "SBU2_B8") (pintype "passive+no_connect"))
    )
    (net (code "102") (name "unconnected-(J1-SSRXn1-PadB10)") (class "Default")
      (node (ref "J1") (pin "B10") (pinfunction "SSRXn1_B10") (pintype "passive+no_connect"))
    )
    (net (code "103") (name "unconnected-(J1-SSRXn2-PadA10)") (class "Default")
      (node (ref "J1") (pin "A10") (pinfunction "SSRXn2_A10") (pintype "passive+no_connect"))
    )
    (net (code "104") (name "unconnected-(J1-SSRXp1-PadB11)") (class "Default")
      (node (ref "J1") (pin "B11") (pinfunction "SSRXp1_B11") (pintype "passive+no_connect"))
    )
    (net (code "105") (name "unconnected-(J1-SSRXp2-PadA11)") (class "Default")
      (node (ref "J1") (pin "A11") (pinfunction "SSRXp2_A11") (pintype "passive+no_connect"))
    )
    (net (code "106") (name "unconnected-(J1-SSTXn1-PadA3)") (class "Default")
      (node (ref "J1") (pin "A3") (pinfunction "SSTXn1_A3") (pintype "passive+no_connect"))
    )
    (net (code "107") (name "unconnected-(J1-SSTXn2-PadB3)") (class "Default")
      (node (ref "J1") (pin "B3") (pinfunction "SSTXn2_B3") (pintype "passive+no_connect"))
    )
    (net (code "108") (name "unconnected-(J1-SSTXp1-PadA2)") (class "Default")
      (node (ref "J1") (pin "A2") (pinfunction "SSTXp1_A2") (pintype "passive+no_connect"))
    )
    (net (code "109") (name "unconnected-(J1-SSTXp2-PadB2)") (class "Default")
      (node (ref "J1") (pin "B2") (pinfunction "SSTXp2_B2") (pintype "passive+no_connect"))
    )
    (net (code "110") (name "unconnected-(J1-VCONN-PadB5)") (class "Default")
      (node (ref "J1") (pin "B5") (pinfunction "VCONN_B5") (pintype "passive+no_connect"))
    )
    (net (code "111") (name "unconnected-(U3-1~{OE}-Pad1)") (class "Default")
      (node (ref "U3") (pin "1") (pinfunction "1~{OE}_1") (pintype "output+no_connect"))
    )
    (net (code "112") (name "unconnected-(U3-2~{OE}-Pad4)") (class "Default")
      (node (ref "U3") (pin "4") (pinfunction "2~{OE}_4") (pintype "output+no_connect"))
    )
    (net (code "113") (name "unconnected-(U3-3~{OE}-Pad10)") (class "Default")
      (node (ref "U3") (pin "10") (pinfunction "3~{OE}_10") (pintype "output+no_connect"))
    )
    (net (code "114") (name "unconnected-(U3-4A-Pad12)") (class "Default")
      (node (ref "U3") (pin "12") (pinfunction "4A_12") (pintype "input+no_connect"))
    )
    (net (code "115") (name "unconnected-(U3-4Y-Pad11)") (class "Default")
      (node (ref "U3") (pin "11") (pinfunction "4Y_11") (pintype "output+no_connect"))
    )
    (net (code "116") (name "unconnected-(U3-4~{OE}-Pad13)") (class "Default")
      (node (ref "U3") (pin "13") (pinfunction "4~{OE}_13") (pintype "output+no_connect"))
    )
    (net (code "117") (name "unconnected-(U5-OSCIN_PA1-Pad5)") (class "Default")
      (node (ref "U5") (pin "5") (pinfunction "OSCIN_PA1_5") (pintype "bidirectional+no_connect"))
    )
    (net (code "118") (name "unconnected-(U5-OSCOUT{slash}PA2-Pad6)") (class "Default")
      (node (ref "U5") (pin "6") (pinfunction "OSCOUT/PA2_6") (pintype "bidirectional+no_connect"))
    )
    (net (code "119") (name "unconnected-(U5-PB4(T){slash}I2C_SCL[ADC_ETR]-Pad12)") (class "Default")
      (node (ref "U5") (pin "12") (pinfunction "PB4(T)/I2C_SCL[ADC_ETR]_12") (pintype "bidirectional+no_connect"))
    )
    (net (code "120") (name "unconnected-(U5-PB5(T){slash}I2C_SDA[TIM1_BKIN]-Pad11)") (class "Default")
      (node (ref "U5") (pin "11") (pinfunction "PB5(T)/I2C_SDA[TIM1_BKIN]_11") (pintype "bidirectional+no_connect"))
    )
    (net (code "121") (name "unconnected-(U5-PC3(HS){slash}TIM1_CH3[TLI][TIM1_CH1N]-Pad13)") (class "Default")
      (node (ref "U5") (pin "13") (pinfunction "PC3(HS)/TIM1_CH3[TLI][TIM1_CH1N]_13") (pintype "bidirectional+no_connect"))
    )
    (net (code "122") (name "unconnected-(U5-PC7(HS){slash}SPI_MISO[TIM1_CH2]-Pad17)") (class "Default")
      (node (ref "U5") (pin "17") (pinfunction "PC7(HS)/SPI_MISO[TIM1_CH2]_17") (pintype "bidirectional+no_connect"))
    )
    (net (code "123") (name "unconnected-(U5-PD2(HS){slash}AIN3{slash}[TIM2_CH3]-Pad19)") (class "Default")
      (node (ref "U5") (pin "19") (pinfunction "PD2(HS)/AIN3/[TIM2_CH3]_19") (pintype "bidirectional+no_connect"))
    )
    (net (code "124") (name "unconnected-(U5-PD3(HS){slash}AIN4{slash}TIM2_CH2{slash}ADC_ETR-Pad20)") (class "Default")
      (node (ref "U5") (pin "20") (pinfunction "PD3(HS)/AIN4/TIM2_CH2/ADC_ETR_20") (pintype "bidirectional+no_connect"))
    )
    (net (code "125") (name "unconnected-(U5-UART1_CK{slash}TIM2_CH1{slash}BEEP{slash}(HS)PD4-Pad1)") (class "Default")
      (node (ref "U5") (pin "1") (pinfunction "UART1_CK/TIM2_CH1/BEEP/(HS)PD4_1") (pintype "bidirectional+no_connect"))
    )
    (net (code "126") (name "unconnected-(U5-UART1_RX{slash}AIN6{slash}(HS)PD6-Pad3)") (class "Default")
      (node (ref "U5") (pin "3") (pinfunction "UART1_RX/AIN6/(HS)PD6_3") (pintype "bidirectional+no_connect"))
    )
    (net (code "127") (name "unconnected-(U5-UART1_TX{slash}AIN5{slash}(HS)PD5-Pad2)") (class "Default")
      (node (ref "U5") (pin "2") (pinfunction "UART1_TX/AIN5/(HS)PD5_2") (pintype "bidirectional+no_connect"))
    )
    (net (code "128") (name "unconnected-(U7-DOUT-Pad24)") (class "Default")
      (node (ref "U7") (pin "24") (pinfunction "DOUT_24") (pintype "output"))
    )
  )
)
